# SparkSwitch.net
KiCad netlist of a schematic drawn in EAGLE
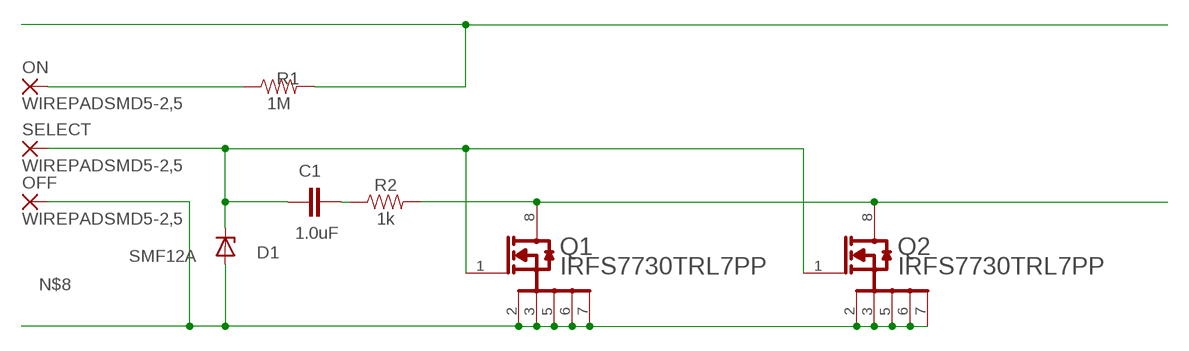
[diagram p0: schematic, sheet 1]

(export (version "E")
  (design (tool "Eeschema 10.0.6"))
  (components
    (comp (ref "C1")
      (value "1.0uF")
      (footprint "eagle-import:0805")
      (libsource (lib "eagle-import") (part "1.0UF-0805-25V-(+80/-20%)"))
    )
    (comp (ref "D1")
      (value "SMF12A")
      (footprint "eagle-import:SOD123F")
      (fields (field (name "MF") "Littelfuse"))
      (libsource (lib "eagle-import") (part "SMFA12"))
    )
    (comp (ref "OFF")
      (value "WIREPADSMD5-2,5")
      (footprint "eagle-import:5-2,5")
      (libsource (lib "eagle-import") (part "WIREPADSMD5-2,5"))
    )
    (comp (ref "ON")
      (value "WIREPADSMD5-2,5")
      (footprint "eagle-import:5-2,5")
      (libsource (lib "eagle-import") (part "WIREPADSMD5-2,5"))
    )
    (comp (ref "Q1")
      (value "INFINEON_IRFS7730TRL7PPINFINEON_IRFS7730TRL7PP_0_0")
      (footprint "eagle-import:INFINEON_IRFS7730TRL7PP_0")
      (fields
        (field (name "DIGIKEY_PART_NUMBER") "IRFS7730TRL7PPCT-ND")
        (field (name "MF") "Infineon")
        (field (name "MOUSER_PART_NUMBER") "942-IRFS7730TRL7PP")
      )
      (libsource (lib "eagle-import") (part "INFINEON_IRFS7730TRL7PPINFINEON_IRFS7730TRL7PP_0_0"))
    )
    (comp (ref "Q2")
      (value "INFINEON_IRFS7730TRL7PPINFINEON_IRFS7730TRL7PP_0_0")
      (footprint "eagle-import:INFINEON_IRFS7730TRL7PP_0")
      (fields
        (field (name "DIGIKEY_PART_NUMBER") "IRFS7730TRL7PPCT-ND")
        (field (name "MF") "Infineon")
        (field (name "MOUSER_PART_NUMBER") "942-IRFS7730TRL7PP")
      )
      (libsource (lib "eagle-import") (part "INFINEON_IRFS7730TRL7PPINFINEON_IRFS7730TRL7PP_0_0"))
    )
    (comp (ref "R1")
      (value "1M")
      (footprint "eagle-import:0603")
      (libsource (lib "eagle-import") (part "1MOHM-0603-1/4W-5%"))
    )
    (comp (ref "R2")
      (value "1k")
      (footprint "eagle-import:0603")
      (libsource (lib "eagle-import") (part "1KOHM-0603-1/10W-1%"))
    )
    (comp (ref "SELECT")
      (value "WIREPADSMD5-2,5")
      (footprint "eagle-import:5-2,5")
      (libsource (lib "eagle-import") (part "WIREPADSMD5-2,5"))
    )
  )
  (nets
    (net (code "1") (name "/N$8") (class "Default")
      (node (ref "D1") (pin "A") (pinfunction "A_A") (pintype "passive"))
      (node (ref "OFF") (pin "1") (pinfunction "P_1") (pintype "passive"))
      (node (ref "Q1") (pin "2") (pinfunction "1_S_2") (pintype "passive"))
      (node (ref "Q1") (pin "3") (pinfunction "2_S_3") (pintype "passive"))
      (node (ref "Q1") (pin "5") (pinfunction "3_S_5") (pintype "passive"))
      (node (ref "Q1") (pin "6") (pinfunction "4_S_6") (pintype "passive"))
      (node (ref "Q1") (pin "7") (pinfunction "5_S_7") (pintype "passive"))
      (node (ref "Q2") (pin "2") (pinfunction "1_S_2") (pintype "passive"))
      (node (ref "Q2") (pin "3") (pinfunction "2_S_3") (pintype "passive"))
      (node (ref "Q2") (pin "5") (pinfunction "3_S_5") (pintype "passive"))
      (node (ref "Q2") (pin "6") (pinfunction "4_S_6") (pintype "passive"))
      (node (ref "Q2") (pin "7") (pinfunction "5_S_7") (pintype "passive"))
    )
    (net (code "2") (name "Net-(C1-Pad2)") (class "Default")
      (node (ref "C1") (pin "2") (pinfunction "2_2") (pintype "passive"))
      (node (ref "R2") (pin "1") (pinfunction "1_1") (pintype "passive"))
    )
    (net (code "3") (name "Net-(ON-P)") (class "Default")
      (node (ref "ON") (pin "1") (pinfunction "P_1") (pintype "passive"))
      (node (ref "R1") (pin "1") (pinfunction "1_1") (pintype "passive"))
    )
    (net (code "4") (name "Net-(Q1-D)") (class "Default")
      (node (ref "Q1") (pin "8") (pinfunction "D_8") (pintype "passive"))
      (node (ref "Q2") (pin "8") (pinfunction "D_8") (pintype "passive"))
      (node (ref "R2") (pin "2") (pinfunction "2_2") (pintype "passive"))
    )
    (net (code "5") (name "Net-(Q1-G)") (class "Default")
      (node (ref "C1") (pin "1") (pinfunction "1_1") (pintype "passive"))
      (node (ref "D1") (pin "C") (pinfunction "C_C") (pintype "passive"))
      (node (ref "Q1") (pin "1") (pinfunction "G_1") (pintype "passive"))
      (node (ref "Q2") (pin "1") (pinfunction "G_1") (pintype "passive"))
      (node (ref "SELECT") (pin "1") (pinfunction "P_1") (pintype "passive"))
    )
    (net (code "6") (name "unconnected-(R1-Pad2)") (class "Default")
      (node (ref "R1") (pin "2") (pinfunction "2_2") (pintype "passive"))
    )
  )
)
